# 4G.net
KiCad netlist of a schematic drawn in Altium Designer
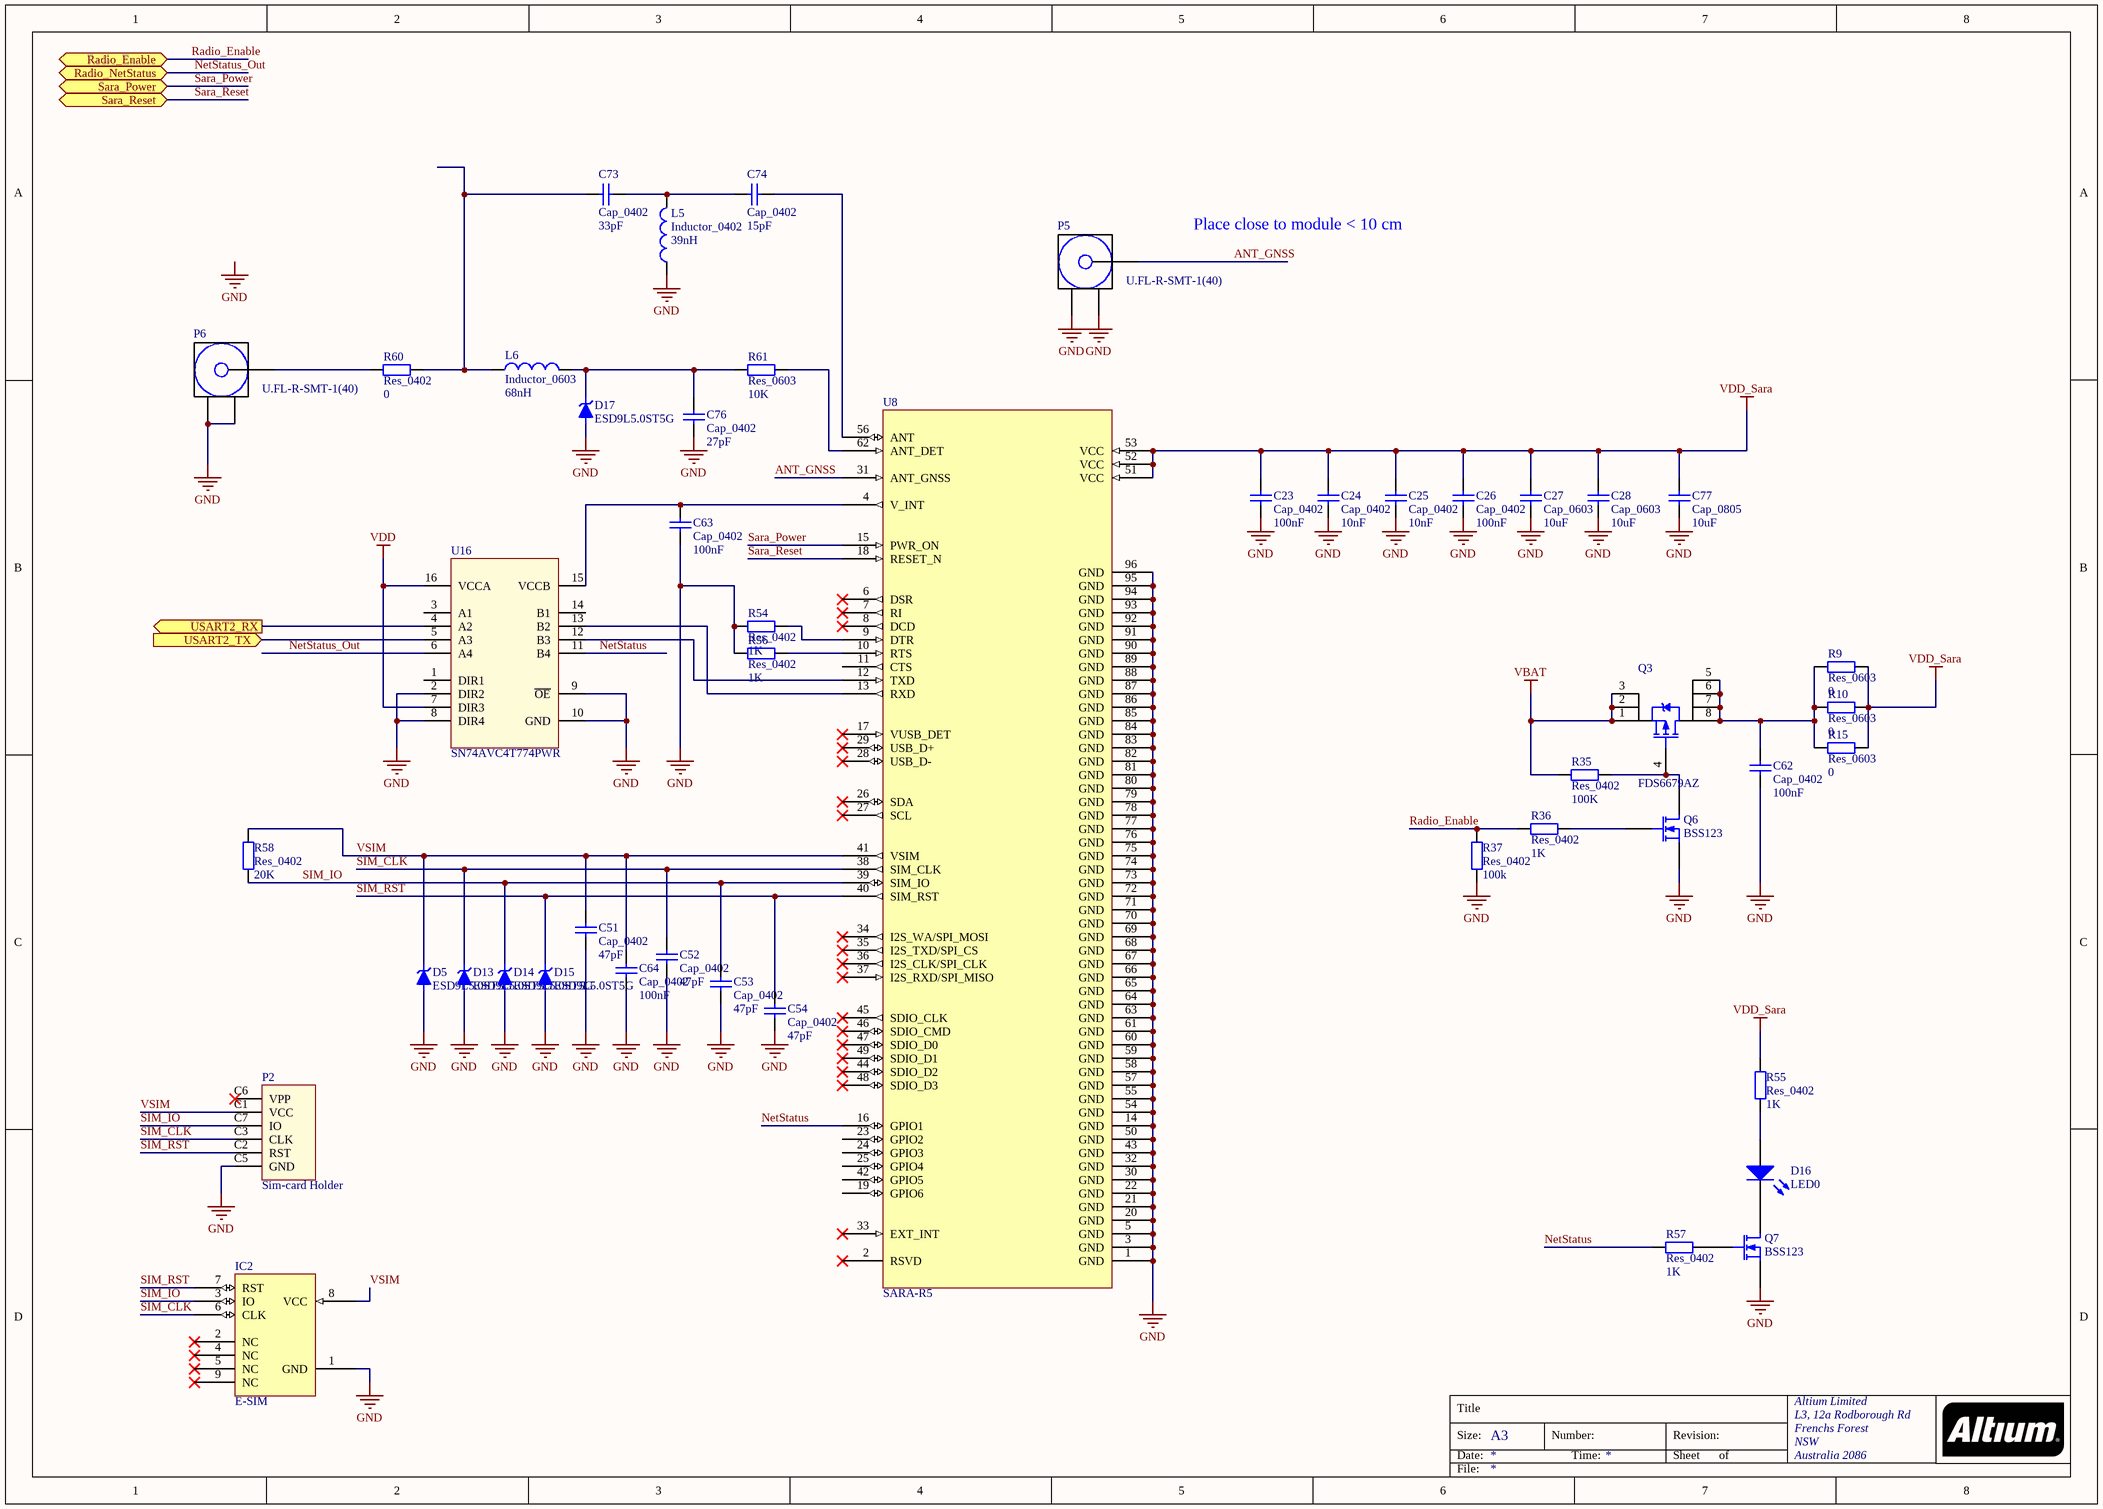
[diagram p0: 4G.SchDoc]

(export (version "E")
  (design (tool "Eeschema 10.0.6"))
  (components
    (comp (ref "C23")
      (value "Cap_0402")
      (footprint "0402")
      (description "Capacitor")
      (fields (field (name "ALTIUM_VALUE") "100nF") (field (name "PUBLISHER") "Altium Limited"))
      (libsource (lib "Schematic_Components") (part "Cap_0402"))
    )
    (comp (ref "C24")
      (value "Cap_0402")
      (footprint "0402")
      (description "Capacitor")
      (fields (field (name "ALTIUM_VALUE") "10nF") (field (name "PUBLISHER") "Altium Limited"))
      (libsource (lib "Schematic_Components") (part "Cap_0402"))
    )
    (comp (ref "C25")
      (value "Cap_0402")
      (footprint "0402")
      (description "Capacitor")
      (fields (field (name "ALTIUM_VALUE") "10nF") (field (name "PUBLISHER") "Altium Limited"))
      (libsource (lib "Schematic_Components") (part "Cap_0402"))
    )
    (comp (ref "C26")
      (value "Cap_0402")
      (footprint "0402")
      (description "Capacitor")
      (fields (field (name "ALTIUM_VALUE") "100nF") (field (name "PUBLISHER") "Altium Limited"))
      (libsource (lib "Schematic_Components") (part "Cap_0402"))
    )
    (comp (ref "C27")
      (value "Cap_0603")
      (footprint "0603")
      (description "Capacitor")
      (fields (field (name "ALTIUM_VALUE") "10uF") (field (name "PUBLISHER") "Altium Limited"))
      (libsource (lib "Schematic_Components") (part "Cap_0603"))
    )
    (comp (ref "C28")
      (value "Cap_0603")
      (footprint "0603")
      (description "Capacitor")
      (fields (field (name "ALTIUM_VALUE") "10uF") (field (name "PUBLISHER") "Altium Limited"))
      (libsource (lib "Schematic_Components") (part "Cap_0603"))
    )
    (comp (ref "C51")
      (value "Cap_0402")
      (footprint "0402")
      (description "Capacitor")
      (fields (field (name "ALTIUM_VALUE") "47pF") (field (name "PUBLISHER") "Altium Limited"))
      (libsource (lib "Schematic_Components") (part "Cap_0402"))
    )
    (comp (ref "C52")
      (value "Cap_0402")
      (footprint "0402")
      (description "Capacitor")
      (fields (field (name "ALTIUM_VALUE") "47pF") (field (name "PUBLISHER") "Altium Limited"))
      (libsource (lib "Schematic_Components") (part "Cap_0402"))
    )
    (comp (ref "C53")
      (value "Cap_0402")
      (footprint "0402")
      (description "Capacitor")
      (fields (field (name "ALTIUM_VALUE") "47pF") (field (name "PUBLISHER") "Altium Limited"))
      (libsource (lib "Schematic_Components") (part "Cap_0402"))
    )
    (comp (ref "C54")
      (value "Cap_0402")
      (footprint "0402")
      (description "Capacitor")
      (fields (field (name "ALTIUM_VALUE") "47pF") (field (name "PUBLISHER") "Altium Limited"))
      (libsource (lib "Schematic_Components") (part "Cap_0402"))
    )
    (comp (ref "C62")
      (value "Cap_0402")
      (footprint "0402")
      (description "Capacitor")
      (fields (field (name "ALTIUM_VALUE") "100nF") (field (name "PUBLISHER") "Altium Limited"))
      (libsource (lib "Schematic_Components") (part "Cap_0402"))
    )
    (comp (ref "C63")
      (value "Cap_0402")
      (footprint "0402")
      (description "Capacitor")
      (fields (field (name "ALTIUM_VALUE") "100nF") (field (name "PUBLISHER") "Altium Limited"))
      (libsource (lib "Schematic_Components") (part "Cap_0402"))
    )
    (comp (ref "C64")
      (value "Cap_0402")
      (footprint "0402")
      (description "Capacitor")
      (fields (field (name "ALTIUM_VALUE") "100nF") (field (name "PUBLISHER") "Altium Limited"))
      (libsource (lib "Schematic_Components") (part "Cap_0402"))
    )
    (comp (ref "C73")
      (value "Cap_0402")
      (footprint "0402")
      (description "Capacitor")
      (fields (field (name "ALTIUM_VALUE") "33pF") (field (name "PUBLISHER") "Altium Limited"))
      (libsource (lib "Schematic_Components") (part "Cap_0402"))
    )
    (comp (ref "C74")
      (value "Cap_0402")
      (footprint "0402")
      (description "Capacitor")
      (fields (field (name "ALTIUM_VALUE") "15pF") (field (name "PUBLISHER") "Altium Limited"))
      (libsource (lib "Schematic_Components") (part "Cap_0402"))
    )
    (comp (ref "C76")
      (value "Cap_0402")
      (footprint "0402")
      (description "Capacitor")
      (fields (field (name "ALTIUM_VALUE") "27pF") (field (name "PUBLISHER") "Altium Limited"))
      (libsource (lib "Schematic_Components") (part "Cap_0402"))
    )
    (comp (ref "C77")
      (value "Cap_0805")
      (footprint "0805")
      (description "Capacitor")
      (fields (field (name "ALTIUM_VALUE") "10uF") (field (name "PUBLISHER") "Altium Limited"))
      (libsource (lib "Schematic_Components") (part "Cap_0805"))
    )
    (comp (ref "D5")
      (value "ESD9L5.0ST5G")
      (footprint "SODFL100X40-2N")
      (description "TVS_ESD9L5-0ST5G")
      (libsource (lib "Exeger_schematic_library") (part "ESD9L5-0ST5G"))
    )
    (comp (ref "D13")
      (value "ESD9L5.0ST5G")
      (footprint "SODFL100X40-2N")
      (description "TVS_ESD9L5-0ST5G")
      (libsource (lib "Exeger_schematic_library") (part "ESD9L5-0ST5G"))
    )
    (comp (ref "D14")
      (value "ESD9L5.0ST5G")
      (footprint "SODFL100X40-2N")
      (description "TVS_ESD9L5-0ST5G")
      (libsource (lib "Exeger_schematic_library") (part "ESD9L5-0ST5G"))
    )
    (comp (ref "D15")
      (value "ESD9L5.0ST5G")
      (footprint "SODFL100X40-2N")
      (description "TVS_ESD9L5-0ST5G")
      (libsource (lib "Exeger_schematic_library") (part "ESD9L5-0ST5G"))
    )
    (comp (ref "D16")
      (value "LED0")
      (footprint "0603")
      (description "Typical INFRARED GaAs LED")
      (fields (field (name "PUBLISHER") "Altium Limited"))
      (libsource (lib "Schematic_Components") (part "LED0"))
    )
    (comp (ref "D17")
      (value "ESD9L5.0ST5G")
      (footprint "SODFL100X40-2N")
      (description "TVS_ESD9L5-0ST5G")
      (libsource (lib "Exeger_schematic_library") (part "ESD9L5-0ST5G"))
    )
    (comp (ref "IC2")
      (value "E-SIM")
      (footprint "MFF2-ESIM")
      (description "E-Sim")
      (libsource (lib "Schematic_Components") (part "E-SIM"))
    )
    (comp (ref "L5")
      (value "Inductor_0402")
      (footprint "0402")
      (description "Inductor")
      (fields (field (name "ALTIUM_VALUE") "39nH"))
      (libsource (lib "Schematic_Components") (part "Inductor_0402"))
    )
    (comp (ref "L6")
      (value "Inductor_0603")
      (footprint "0603")
      (description "Inductor")
      (fields (field (name "ALTIUM_VALUE") "68nH"))
      (libsource (lib "Schematic_Components") (part "Inductor_0603"))
    )
    (comp (ref "P2")
      (value "Sim-card Holder")
      (footprint "Sim-card Holder")
      (description "788000001_Molex")
      (libsource (lib "Exeger_schematic_library") (part "Sim-card Holder"))
    )
    (comp (ref "P5")
      (value "U.FL-R-SMT-1(40)")
      (footprint "U.FL-R-SMT-1(40)")
      (description "RF-Connector")
      (libsource (lib "Exeger_schematic_library") (part "RF-Connector"))
    )
    (comp (ref "P6")
      (value "U.FL-R-SMT-1(40)")
      (footprint "U.FL-R-SMT-1(40)")
      (description "RF-Connector")
      (libsource (lib "Exeger_schematic_library") (part "RF-Connector"))
    )
    (comp (ref "Q3")
      (value "FDS6679AZ")
      (footprint "SOIC127P600X175-8N")
      (description "Transistor, FET")
      (libsource (lib "Exeger_schematic_library") (part "FDS6679AZ"))
    )
    (comp (ref "Q6")
      (value "BSS123")
      (footprint "SOT-23")
      (description "N-Channel MOSFET")
      (fields (field (name "PUBLISHER") "Altium Limited"))
      (libsource (lib "Schematic_Components") (part "BSS123"))
    )
    (comp (ref "Q7")
      (value "BSS123")
      (footprint "SOT-23")
      (description "N-Channel MOSFET")
      (fields (field (name "PUBLISHER") "Altium Limited"))
      (libsource (lib "Schematic_Components") (part "BSS123"))
    )
    (comp (ref "R9")
      (value "Res_0603")
      (footprint "0603")
      (description "Resistor")
      (fields (field (name "ALTIUM_VALUE") "0") (field (name "PUBLISHER") "Altium Limited"))
      (libsource (lib "Schematic_Components") (part "Res_0603"))
    )
    (comp (ref "R10")
      (value "Res_0603")
      (footprint "0603")
      (description "Resistor")
      (fields (field (name "ALTIUM_VALUE") "0") (field (name "PUBLISHER") "Altium Limited"))
      (libsource (lib "Schematic_Components") (part "Res_0603"))
    )
    (comp (ref "R15")
      (value "Res_0603")
      (footprint "0603")
      (description "Resistor")
      (fields (field (name "ALTIUM_VALUE") "0") (field (name "PUBLISHER") "Altium Limited"))
      (libsource (lib "Schematic_Components") (part "Res_0603"))
    )
    (comp (ref "R35")
      (value "Res_0402")
      (footprint "0402")
      (description "Resistor")
      (fields (field (name "ALTIUM_VALUE") "100K") (field (name "PUBLISHER") "Altium Limited"))
      (libsource (lib "Schematic_Components") (part "Res_0402"))
    )
    (comp (ref "R36")
      (value "Res_0402")
      (footprint "0402")
      (description "Resistor")
      (fields (field (name "ALTIUM_VALUE") "1K") (field (name "PUBLISHER") "Altium Limited"))
      (libsource (lib "Schematic_Components") (part "Res_0402"))
    )
    (comp (ref "R37")
      (value "Res_0402")
      (footprint "0402")
      (description "Resistor")
      (fields (field (name "ALTIUM_VALUE") "100k") (field (name "PUBLISHER") "Altium Limited"))
      (libsource (lib "") (part "Res_0402_1"))
    )
    (comp (ref "R54")
      (value "Res_0402")
      (footprint "0402")
      (description "Resistor")
      (fields (field (name "ALTIUM_VALUE") "1K") (field (name "PUBLISHER") "Altium Limited"))
      (libsource (lib "Schematic_Components") (part "Res_0402"))
    )
    (comp (ref "R55")
      (value "Res_0402")
      (footprint "0402")
      (description "Resistor")
      (fields (field (name "ALTIUM_VALUE") "1K") (field (name "PUBLISHER") "Altium Limited"))
      (libsource (lib "") (part "Res_0402_1"))
    )
    (comp (ref "R56")
      (value "Res_0402")
      (footprint "0402")
      (description "Resistor")
      (fields (field (name "ALTIUM_VALUE") "1K") (field (name "PUBLISHER") "Altium Limited"))
      (libsource (lib "Schematic_Components") (part "Res_0402"))
    )
    (comp (ref "R57")
      (value "Res_0402")
      (footprint "0402")
      (description "Resistor")
      (fields (field (name "ALTIUM_VALUE") "1K") (field (name "PUBLISHER") "Altium Limited"))
      (libsource (lib "Schematic_Components") (part "Res_0402"))
    )
    (comp (ref "R58")
      (value "Res_0402")
      (footprint "0402")
      (description "Resistor")
      (fields (field (name "ALTIUM_VALUE") "20K") (field (name "PUBLISHER") "Altium Limited"))
      (libsource (lib "") (part "Res_0402_1"))
    )
    (comp (ref "R60")
      (value "Res_0402")
      (footprint "0402")
      (description "Resistor")
      (fields (field (name "ALTIUM_VALUE") "0") (field (name "PUBLISHER") "Altium Limited"))
      (libsource (lib "Schematic_Components") (part "Res_0402"))
    )
    (comp (ref "R61")
      (value "Res_0603")
      (footprint "0603")
      (description "Resistor")
      (fields (field (name "ALTIUM_VALUE") "10K") (field (name "PUBLISHER") "Altium Limited"))
      (libsource (lib "Schematic_Components") (part "Res_0603"))
    )
    (comp (ref "U8")
      (value "SARA-R5")
      (footprint "SARA-XX")
      (description "Sara-R5")
      (libsource (lib "Schematic_Components") (part "SARA-R5"))
    )
    (comp (ref "U16")
      (value "SN74AVC4T774PWR")
      (footprint "TSOP65P640X120-16N")
      (description "Buffer")
      (libsource (lib "Exeger_schematic_library") (part "SN74AVC4T774PWR"))
    )
  )
  (nets
    (net (code "1") (name "/ANT_GNSS") (class "Default")
      (node (ref "P5") (pin "1") (pinfunction "1_1") (pintype "passive"))
      (node (ref "U8") (pin "31") (pinfunction "ANT_GNSS_31") (pintype "input"))
    )
    (net (code "2") (name "/NetStatus") (class "Default")
      (node (ref "R57") (pin "1") (pinfunction "1_1") (pintype "passive"))
      (node (ref "U16") (pin "11") (pinfunction "B4_11") (pintype "passive"))
      (node (ref "U8") (pin "16") (pinfunction "GPIO1_16") (pintype "bidirectional"))
    )
    (net (code "3") (name "/NetStatus_Out") (class "Default")
      (node (ref "U16") (pin "6") (pinfunction "A4_6") (pintype "passive"))
    )
    (net (code "4") (name "/Radio_Enable") (class "Default")
      (node (ref "R36") (pin "1") (pinfunction "1_1") (pintype "passive"))
      (node (ref "R37") (pin "2") (pinfunction "2_2") (pintype "passive"))
    )
    (net (code "5") (name "/SIM_CLK") (class "Default")
      (node (ref "C52") (pin "2") (pinfunction "2_2") (pintype "passive"))
      (node (ref "D13") (pin "1") (pinfunction "1_1") (pintype "passive"))
      (node (ref "IC2") (pin "6") (pinfunction "CLK_6") (pintype "bidirectional"))
      (node (ref "P2") (pin "C3") (pinfunction "CLK_C3") (pintype "passive"))
      (node (ref "U8") (pin "38") (pinfunction "SIM_CLK_38") (pintype "output"))
    )
    (net (code "6") (name "/SIM_IO") (class "Default")
      (node (ref "C53") (pin "2") (pinfunction "2_2") (pintype "passive"))
      (node (ref "D14") (pin "1") (pinfunction "1_1") (pintype "passive"))
      (node (ref "IC2") (pin "3") (pinfunction "IO_3") (pintype "bidirectional"))
      (node (ref "P2") (pin "C7") (pinfunction "IO_C7") (pintype "passive"))
      (node (ref "R58") (pin "1") (pinfunction "1_1") (pintype "passive"))
      (node (ref "U8") (pin "39") (pinfunction "SIM_IO_39") (pintype "bidirectional"))
    )
    (net (code "7") (name "/SIM_RST") (class "Default")
      (node (ref "C54") (pin "2") (pinfunction "2_2") (pintype "passive"))
      (node (ref "D15") (pin "1") (pinfunction "1_1") (pintype "passive"))
      (node (ref "IC2") (pin "7") (pinfunction "RST_7") (pintype "bidirectional"))
      (node (ref "P2") (pin "C2") (pinfunction "RST_C2") (pintype "passive"))
      (node (ref "U8") (pin "40") (pinfunction "SIM_RST_40") (pintype "output"))
    )
    (net (code "8") (name "/Sara_Power") (class "Default")
      (node (ref "U8") (pin "15") (pinfunction "PWR_ON_15") (pintype "input"))
    )
    (net (code "9") (name "/Sara_Reset") (class "Default")
      (node (ref "U8") (pin "18") (pinfunction "RESET_N_18") (pintype "input"))
    )
    (net (code "10") (name "/USART2_RX") (class "Default")
      (node (ref "U16") (pin "4") (pinfunction "A2_4") (pintype "passive"))
    )
    (net (code "11") (name "/USART2_TX") (class "Default")
      (node (ref "U16") (pin "5") (pinfunction "A3_5") (pintype "passive"))
    )
    (net (code "12") (name "/VSIM") (class "Default")
      (node (ref "C51") (pin "2") (pinfunction "2_2") (pintype "passive"))
      (node (ref "C64") (pin "2") (pinfunction "2_2") (pintype "passive"))
      (node (ref "D5") (pin "1") (pinfunction "1_1") (pintype "passive"))
      (node (ref "IC2") (pin "8") (pinfunction "VCC_8") (pintype "input"))
      (node (ref "P2") (pin "C1") (pinfunction "VCC_C1") (pintype "passive"))
      (node (ref "R58") (pin "2") (pinfunction "2_2") (pintype "passive"))
      (node (ref "U8") (pin "41") (pinfunction "VSIM_41") (pintype "output"))
    )
    (net (code "13") (name "GND") (class "Default")
      (node (ref "C23") (pin "1") (pinfunction "1_1") (pintype "passive"))
      (node (ref "C24") (pin "1") (pinfunction "1_1") (pintype "passive"))
      (node (ref "C25") (pin "1") (pinfunction "1_1") (pintype "passive"))
      (node (ref "C26") (pin "1") (pinfunction "1_1") (pintype "passive"))
      (node (ref "C27") (pin "1") (pinfunction "1_1") (pintype "passive"))
      (node (ref "C28") (pin "1") (pinfunction "1_1") (pintype "passive"))
      (node (ref "C51") (pin "1") (pinfunction "1_1") (pintype "passive"))
      (node (ref "C52") (pin "1") (pinfunction "1_1") (pintype "passive"))
      (node (ref "C53") (pin "1") (pinfunction "1_1") (pintype "passive"))
      (node (ref "C54") (pin "1") (pinfunction "1_1") (pintype "passive"))
      (node (ref "C62") (pin "1") (pinfunction "1_1") (pintype "passive"))
      (node (ref "C63") (pin "1") (pinfunction "1_1") (pintype "passive"))
      (node (ref "C64") (pin "1") (pinfunction "1_1") (pintype "passive"))
      (node (ref "C76") (pin "1") (pinfunction "1_1") (pintype "passive"))
      (node (ref "C77") (pin "1") (pinfunction "1_1") (pintype "passive"))
      (node (ref "D13") (pin "2") (pinfunction "2_2") (pintype "passive"))
      (node (ref "D14") (pin "2") (pinfunction "2_2") (pintype "passive"))
      (node (ref "D15") (pin "2") (pinfunction "2_2") (pintype "passive"))
      (node (ref "D17") (pin "2") (pinfunction "2_2") (pintype "passive"))
      (node (ref "D5") (pin "2") (pinfunction "2_2") (pintype "passive"))
      (node (ref "IC2") (pin "1") (pinfunction "GND_1") (pintype "passive"))
      (node (ref "L5") (pin "1") (pinfunction "1_1") (pintype "passive"))
      (node (ref "P2") (pin "C5") (pinfunction "GND_C5") (pintype "passive"))
      (node (ref "P5") (pin "2") (pinfunction "2_2") (pintype "passive"))
      (node (ref "P5") (pin "3") (pinfunction "3_3") (pintype "passive"))
      (node (ref "P6") (pin "2") (pinfunction "2_2") (pintype "passive"))
      (node (ref "P6") (pin "3") (pinfunction "3_3") (pintype "passive"))
      (node (ref "Q6") (pin "2") (pinfunction "S_2") (pintype "passive"))
      (node (ref "Q7") (pin "2") (pinfunction "S_2") (pintype "passive"))
      (node (ref "R37") (pin "1") (pinfunction "1_1") (pintype "passive"))
      (node (ref "R54") (pin "1") (pinfunction "1_1") (pintype "passive"))
      (node (ref "R56") (pin "1") (pinfunction "1_1") (pintype "passive"))
      (node (ref "U16") (pin "10") (pinfunction "GND_10") (pintype "passive"))
      (node (ref "U16") (pin "2") (pinfunction "DIR2_2") (pintype "passive"))
      (node (ref "U16") (pin "8") (pinfunction "DIR4_8") (pintype "passive"))
      (node (ref "U16") (pin "9") (pinfunction "~{OE}_9") (pintype "passive"))
      (node (ref "U8") (pin "1") (pinfunction "GND_1") (pintype "passive"))
      (node (ref "U8") (pin "14") (pinfunction "GND_14") (pintype "passive"))
      (node (ref "U8") (pin "20") (pinfunction "GND_20") (pintype "passive"))
      (node (ref "U8") (pin "21") (pinfunction "GND_21") (pintype "passive"))
      (node (ref "U8") (pin "22") (pinfunction "GND_22") (pintype "passive"))
      (node (ref "U8") (pin "3") (pinfunction "GND_3") (pintype "passive"))
      (node (ref "U8") (pin "30") (pinfunction "GND_30") (pintype "passive"))
      (node (ref "U8") (pin "32") (pinfunction "GND_32") (pintype "passive"))
      (node (ref "U8") (pin "43") (pinfunction "GND_43") (pintype "passive"))
      (node (ref "U8") (pin "5") (pinfunction "GND_5") (pintype "passive"))
      (node (ref "U8") (pin "50") (pinfunction "GND_50") (pintype "passive"))
      (node (ref "U8") (pin "54") (pinfunction "GND_54") (pintype "passive"))
      (node (ref "U8") (pin "55") (pinfunction "GND_55") (pintype "passive"))
      (node (ref "U8") (pin "57") (pinfunction "GND_57") (pintype "passive"))
      (node (ref "U8") (pin "58") (pinfunction "GND_58") (pintype "passive"))
      (node (ref "U8") (pin "59") (pinfunction "GND_59") (pintype "passive"))
      (node (ref "U8") (pin "60") (pinfunction "GND_60") (pintype "passive"))
      (node (ref "U8") (pin "61") (pinfunction "GND_61") (pintype "passive"))
      (node (ref "U8") (pin "63") (pinfunction "GND_63") (pintype "passive"))
      (node (ref "U8") (pin "64") (pinfunction "GND_64") (pintype "passive"))
      (node (ref "U8") (pin "65") (pinfunction "GND_65") (pintype "passive"))
      (node (ref "U8") (pin "66") (pinfunction "GND_66") (pintype "passive"))
      (node (ref "U8") (pin "67") (pinfunction "GND_67") (pintype "passive"))
      (node (ref "U8") (pin "68") (pinfunction "GND_68") (pintype "passive"))
      (node (ref "U8") (pin "69") (pinfunction "GND_69") (pintype "passive"))
      (node (ref "U8") (pin "70") (pinfunction "GND_70") (pintype "passive"))
      (node (ref "U8") (pin "71") (pinfunction "GND_71") (pintype "passive"))
      (node (ref "U8") (pin "72") (pinfunction "GND_72") (pintype "passive"))
      (node (ref "U8") (pin "73") (pinfunction "GND_73") (pintype "passive"))
      (node (ref "U8") (pin "74") (pinfunction "GND_74") (pintype "passive"))
      (node (ref "U8") (pin "75") (pinfunction "GND_75") (pintype "passive"))
      (node (ref "U8") (pin "76") (pinfunction "GND_76") (pintype "passive"))
      (node (ref "U8") (pin "77") (pinfunction "GND_77") (pintype "passive"))
      (node (ref "U8") (pin "78") (pinfunction "GND_78") (pintype "passive"))
      (node (ref "U8") (pin "79") (pinfunction "GND_79") (pintype "passive"))
      (node (ref "U8") (pin "80") (pinfunction "GND_80") (pintype "passive"))
      (node (ref "U8") (pin "81") (pinfunction "GND_81") (pintype "passive"))
      (node (ref "U8") (pin "82") (pinfunction "GND_82") (pintype "passive"))
      (node (ref "U8") (pin "83") (pinfunction "GND_83") (pintype "passive"))
      (node (ref "U8") (pin "84") (pinfunction "GND_84") (pintype "passive"))
      (node (ref "U8") (pin "85") (pinfunction "GND_85") (pintype "passive"))
      (node (ref "U8") (pin "86") (pinfunction "GND_86") (pintype "passive"))
      (node (ref "U8") (pin "87") (pinfunction "GND_87") (pintype "passive"))
      (node (ref "U8") (pin "88") (pinfunction "GND_88") (pintype "passive"))
      (node (ref "U8") (pin "89") (pinfunction "GND_89") (pintype "passive"))
      (node (ref "U8") (pin "90") (pinfunction "GND_90") (pintype "passive"))
      (node (ref "U8") (pin "91") (pinfunction "GND_91") (pintype "passive"))
      (node (ref "U8") (pin "92") (pinfunction "GND_92") (pintype "passive"))
      (node (ref "U8") (pin "93") (pinfunction "GND_93") (pintype "passive"))
      (node (ref "U8") (pin "94") (pinfunction "GND_94") (pintype "passive"))
      (node (ref "U8") (pin "95") (pinfunction "GND_95") (pintype "passive"))
      (node (ref "U8") (pin "96") (pinfunction "GND_96") (pintype "passive"))
    )
    (net (code "14") (name "Net-(C62-Pad2)") (class "Default")
      (node (ref "C62") (pin "2") (pinfunction "2_2") (pintype "passive"))
      (node (ref "Q3") (pin "5") (pinfunction "D_5") (pintype "passive"))
      (node (ref "Q3") (pin "6") (pinfunction "D_6") (pintype "passive"))
      (node (ref "Q3") (pin "7") (pinfunction "D_7") (pintype "passive"))
      (node (ref "Q3") (pin "8") (pinfunction "D_8") (pintype "passive"))
      (node (ref "R10") (pin "1") (pinfunction "1_1") (pintype "passive"))
      (node (ref "R15") (pin "1") (pinfunction "1_1") (pintype "passive"))
      (node (ref "R9") (pin "1") (pinfunction "1_1") (pintype "passive"))
    )
    (net (code "15") (name "Net-(C73-Pad1)") (class "Default")
      (node (ref "C73") (pin "1") (pinfunction "1_1") (pintype "passive"))
      (node (ref "C74") (pin "1") (pinfunction "1_1") (pintype "passive"))
      (node (ref "L5") (pin "2") (pinfunction "2_2") (pintype "passive"))
    )
    (net (code "16") (name "Net-(C73-Pad2)") (class "Default")
      (node (ref "C73") (pin "2") (pinfunction "2_2") (pintype "passive"))
      (node (ref "L6") (pin "1") (pinfunction "1_1") (pintype "passive"))
      (node (ref "R60") (pin "2") (pinfunction "2_2") (pintype "passive"))
    )
    (net (code "17") (name "Net-(C76-Pad2)") (class "Default")
      (node (ref "C76") (pin "2") (pinfunction "2_2") (pintype "passive"))
      (node (ref "D17") (pin "1") (pinfunction "1_1") (pintype "passive"))
      (node (ref "L6") (pin "2") (pinfunction "2_2") (pintype "passive"))
      (node (ref "R61") (pin "1") (pinfunction "1_1") (pintype "passive"))
    )
    (net (code "18") (name "Net-(D16-A)") (class "Default")
      (node (ref "D16") (pin "2") (pinfunction "A_2") (pintype "passive"))
      (node (ref "R55") (pin "1") (pinfunction "1_1") (pintype "passive"))
    )
    (net (code "19") (name "Net-(D16-K)") (class "Default")
      (node (ref "D16") (pin "1") (pinfunction "K_1") (pintype "passive"))
      (node (ref "Q7") (pin "3") (pinfunction "D_3") (pintype "passive"))
    )
    (net (code "20") (name "Net-(P6-Pad1)") (class "Default")
      (node (ref "P6") (pin "1") (pinfunction "1_1") (pintype "passive"))
      (node (ref "R60") (pin "1") (pinfunction "1_1") (pintype "passive"))
    )
    (net (code "21") (name "Net-(Q3-G)") (class "Default")
      (node (ref "Q3") (pin "4") (pinfunction "G_4") (pintype "passive"))
      (node (ref "Q6") (pin "3") (pinfunction "D_3") (pintype "passive"))
      (node (ref "R35") (pin "2") (pinfunction "2_2") (pintype "passive"))
    )
    (net (code "22") (name "Net-(Q6-G)") (class "Default")
      (node (ref "Q6") (pin "1") (pinfunction "G_1") (pintype "passive"))
      (node (ref "R36") (pin "2") (pinfunction "2_2") (pintype "passive"))
    )
    (net (code "23") (name "Net-(Q7-G)") (class "Default")
      (node (ref "Q7") (pin "1") (pinfunction "G_1") (pintype "passive"))
      (node (ref "R57") (pin "2") (pinfunction "2_2") (pintype "passive"))
    )
    (net (code "24") (name "Net-(U8-ANT)") (class "Default")
      (node (ref "C74") (pin "2") (pinfunction "2_2") (pintype "passive"))
      (node (ref "U8") (pin "56") (pinfunction "ANT_56") (pintype "bidirectional"))
    )
    (net (code "25") (name "Net-(U8-ANT_DET)") (class "Default")
      (node (ref "R61") (pin "2") (pinfunction "2_2") (pintype "passive"))
      (node (ref "U8") (pin "62") (pinfunction "ANT_DET_62") (pintype "input"))
    )
    (net (code "26") (name "Net-(U8-DTR)") (class "Default")
      (node (ref "R54") (pin "2") (pinfunction "2_2") (pintype "passive"))
      (node (ref "U8") (pin "9") (pinfunction "DTR_9") (pintype "input"))
    )
    (net (code "27") (name "Net-(U8-RTS)") (class "Default")
      (node (ref "R56") (pin "2") (pinfunction "2_2") (pintype "passive"))
      (node (ref "U8") (pin "10") (pinfunction "RTS_10") (pintype "input"))
    )
    (net (code "28") (name "Net-(U16-B2)") (class "Default")
      (node (ref "U16") (pin "13") (pinfunction "B2_13") (pintype "passive"))
      (node (ref "U8") (pin "13") (pinfunction "RXD_13") (pintype "output"))
    )
    (net (code "29") (name "Net-(U16-B3)") (class "Default")
      (node (ref "U16") (pin "12") (pinfunction "B3_12") (pintype "passive"))
      (node (ref "U8") (pin "12") (pinfunction "TXD_12") (pintype "input"))
    )
    (net (code "30") (name "Net-(U16-VCCB)") (class "Default")
      (node (ref "C63") (pin "2") (pinfunction "2_2") (pintype "passive"))
      (node (ref "U16") (pin "15") (pinfunction "VCCB_15") (pintype "passive"))
      (node (ref "U8") (pin "4") (pinfunction "V_INT_4") (pintype "output"))
    )
    (net (code "31") (name "VBAT") (class "Default")
      (node (ref "Q3") (pin "1") (pinfunction "S_1") (pintype "passive"))
      (node (ref "Q3") (pin "2") (pinfunction "S_2") (pintype "passive"))
      (node (ref "Q3") (pin "3") (pinfunction "S_3") (pintype "passive"))
      (node (ref "R35") (pin "1") (pinfunction "1_1") (pintype "passive"))
    )
    (net (code "32") (name "VDD") (class "Default")
      (node (ref "U16") (pin "16") (pinfunction "VCCA_16") (pintype "passive"))
      (node (ref "U16") (pin "7") (pinfunction "DIR3_7") (pintype "passive"))
    )
    (net (code "33") (name "VDD_Sara") (class "Default")
      (node (ref "C23") (pin "2") (pinfunction "2_2") (pintype "passive"))
      (node (ref "C24") (pin "2") (pinfunction "2_2") (pintype "passive"))
      (node (ref "C25") (pin "2") (pinfunction "2_2") (pintype "passive"))
      (node (ref "C26") (pin "2") (pinfunction "2_2") (pintype "passive"))
      (node (ref "C27") (pin "2") (pinfunction "2_2") (pintype "passive"))
      (node (ref "C28") (pin "2") (pinfunction "2_2") (pintype "passive"))
      (node (ref "C77") (pin "2") (pinfunction "2_2") (pintype "passive"))
      (node (ref "R10") (pin "2") (pinfunction "2_2") (pintype "passive"))
      (node (ref "R15") (pin "2") (pinfunction "2_2") (pintype "passive"))
      (node (ref "R55") (pin "2") (pinfunction "2_2") (pintype "passive"))
      (node (ref "R9") (pin "2") (pinfunction "2_2") (pintype "passive"))
      (node (ref "U8") (pin "51") (pinfunction "VCC_51") (pintype "input"))
      (node (ref "U8") (pin "52") (pinfunction "VCC_52") (pintype "input"))
      (node (ref "U8") (pin "53") (pinfunction "VCC_53") (pintype "input"))
    )
    (net (code "34") (name "unconnected-(IC2-NC-Pad2)") (class "Default")
      (node (ref "IC2") (pin "2") (pinfunction "NC_2") (pintype "passive+no_connect"))
    )
    (net (code "35") (name "unconnected-(IC2-NC-Pad4)") (class "Default")
      (node (ref "IC2") (pin "4") (pinfunction "NC_4") (pintype "passive+no_connect"))
    )
    (net (code "36") (name "unconnected-(IC2-NC-Pad5)") (class "Default")
      (node (ref "IC2") (pin "5") (pinfunction "NC_5") (pintype "passive+no_connect"))
    )
    (net (code "37") (name "unconnected-(IC2-NC-Pad9)") (class "Default")
      (node (ref "IC2") (pin "9") (pinfunction "NC_9") (pintype "passive+no_connect"))
    )
    (net (code "38") (name "unconnected-(P2-VPP-PadC6)") (class "Default")
      (node (ref "P2") (pin "C6") (pinfunction "VPP_C6") (pintype "passive+no_connect"))
    )
    (net (code "39") (name "unconnected-(U8-CTS-Pad11)") (class "Default")
      (node (ref "U8") (pin "11") (pinfunction "CTS_11") (pintype "output"))
    )
    (net (code "40") (name "unconnected-(U8-DCD-Pad8)") (class "Default")
      (node (ref "U8") (pin "8") (pinfunction "DCD_8") (pintype "output+no_connect"))
    )
    (net (code "41") (name "unconnected-(U8-DSR-Pad6)") (class "Default")
      (node (ref "U8") (pin "6") (pinfunction "DSR_6") (pintype "output+no_connect"))
    )
    (net (code "42") (name "unconnected-(U8-EXT_INT-Pad33)") (class "Default")
      (node (ref "U8") (pin "33") (pinfunction "EXT_INT_33") (pintype "input+no_connect"))
    )
    (net (code "43") (name "unconnected-(U8-GPIO2-Pad23)") (class "Default")
      (node (ref "U8") (pin "23") (pinfunction "GPIO2_23") (pintype "bidirectional"))
    )
    (net (code "44") (name "unconnected-(U8-GPIO3-Pad24)") (class "Default")
      (node (ref "U8") (pin "24") (pinfunction "GPIO3_24") (pintype "bidirectional"))
    )
    (net (code "45") (name "unconnected-(U8-GPIO4-Pad25)") (class "Default")
      (node (ref "U8") (pin "25") (pinfunction "GPIO4_25") (pintype "bidirectional"))
    )
    (net (code "46") (name "unconnected-(U8-GPIO5-Pad42)") (class "Default")
      (node (ref "U8") (pin "42") (pinfunction "GPIO5_42") (pintype "bidirectional"))
    )
    (net (code "47") (name "unconnected-(U8-GPIO6-Pad19)") (class "Default")
      (node (ref "U8") (pin "19") (pinfunction "GPIO6_19") (pintype "bidirectional"))
    )
    (net (code "48") (name "unconnected-(U8-I2S_CLK{slash}SPI_CLK-Pad36)") (class "Default")
      (node (ref "U8") (pin "36") (pinfunction "I2S_CLK/SPI_CLK_36") (pintype "output+no_connect"))
    )
    (net (code "49") (name "unconnected-(U8-I2S_RXD{slash}SPI_MISO-Pad37)") (class "Default")
      (node (ref "U8") (pin "37") (pinfunction "I2S_RXD/SPI_MISO_37") (pintype "input+no_connect"))
    )
    (net (code "50") (name "unconnected-(U8-I2S_TXD{slash}SPI_CS-Pad35)") (class "Default")
      (node (ref "U8") (pin "35") (pinfunction "I2S_TXD/SPI_CS_35") (pintype "output+no_connect"))
    )
    (net (code "51") (name "unconnected-(U8-I2S_WA{slash}SPI_MOSI-Pad34)") (class "Default")
      (node (ref "U8") (pin "34") (pinfunction "I2S_WA/SPI_MOSI_34") (pintype "output+no_connect"))
    )
    (net (code "52") (name "unconnected-(U8-RI-Pad7)") (class "Default")
      (node (ref "U8") (pin "7") (pinfunction "RI_7") (pintype "output+no_connect"))
    )
    (net (code "53") (name "unconnected-(U8-RSVD-Pad2)") (class "Default")
      (node (ref "U8") (pin "2") (pinfunction "RSVD_2") (pintype "passive+no_connect"))
    )
    (net (code "54") (name "unconnected-(U8-SCL-Pad27)") (class "Default")
      (node (ref "U8") (pin "27") (pinfunction "SCL_27") (pintype "output+no_connect"))
    )
    (net (code "55") (name "unconnected-(U8-SDA-Pad26)") (class "Default")
      (node (ref "U8") (pin "26") (pinfunction "SDA_26") (pintype "bidirectional+no_connect"))
    )
    (net (code "56") (name "unconnected-(U8-SDIO_CLK-Pad45)") (class "Default")
      (node (ref "U8") (pin "45") (pinfunction "SDIO_CLK_45") (pintype "output+no_connect"))
    )
    (net (code "57") (name "unconnected-(U8-SDIO_CMD-Pad46)") (class "Default")
      (node (ref "U8") (pin "46") (pinfunction "SDIO_CMD_46") (pintype "bidirectional+no_connect"))
    )
    (net (code "58") (name "unconnected-(U8-SDIO_D0-Pad47)") (class "Default")
      (node (ref "U8") (pin "47") (pinfunction "SDIO_D0_47") (pintype "bidirectional+no_connect"))
    )
    (net (code "59") (name "unconnected-(U8-SDIO_D1-Pad49)") (class "Default")
      (node (ref "U8") (pin "49") (pinfunction "SDIO_D1_49") (pintype "bidirectional+no_connect"))
    )
    (net (code "60") (name "unconnected-(U8-SDIO_D2-Pad44)") (class "Default")
      (node (ref "U8") (pin "44") (pinfunction "SDIO_D2_44") (pintype "bidirectional+no_connect"))
    )
    (net (code "61") (name "unconnected-(U8-SDIO_D3-Pad48)") (class "Default")
      (node (ref "U8") (pin "48") (pinfunction "SDIO_D3_48") (pintype "bidirectional+no_connect"))
    )
    (net (code "62") (name "unconnected-(U8-USB_D+-Pad29)") (class "Default")
      (node (ref "U8") (pin "29") (pinfunction "USB_D+_29") (pintype "bidirectional+no_connect"))
    )
    (net (code "63") (name "unconnected-(U8-USB_D--Pad28)") (class "Default")
      (node (ref "U8") (pin "28") (pinfunction "USB_D-_28") (pintype "bidirectional+no_connect"))
    )
    (net (code "64") (name "unconnected-(U8-VUSB_DET-Pad17)") (class "Default")
      (node (ref "U8") (pin "17") (pinfunction "VUSB_DET_17") (pintype "input+no_connect"))
    )
    (net (code "65") (name "unconnected-(U16-A1-Pad3)") (class "Default")
      (node (ref "U16") (pin "3") (pinfunction "A1_3") (pintype "passive"))
    )
    (net (code "66") (name "unconnected-(U16-B1-Pad14)") (class "Default")
      (node (ref "U16") (pin "14") (pinfunction "B1_14") (pintype "passive"))
    )
    (net (code "67") (name "unconnected-(U16-DIR1-Pad1)") (class "Default")
      (node (ref "U16") (pin "1") (pinfunction "DIR1_1") (pintype "passive"))
    )
  )
)
